# DM1097_LEFT_OV9282.net
KiCad netlist of a schematic drawn in Altium Designer
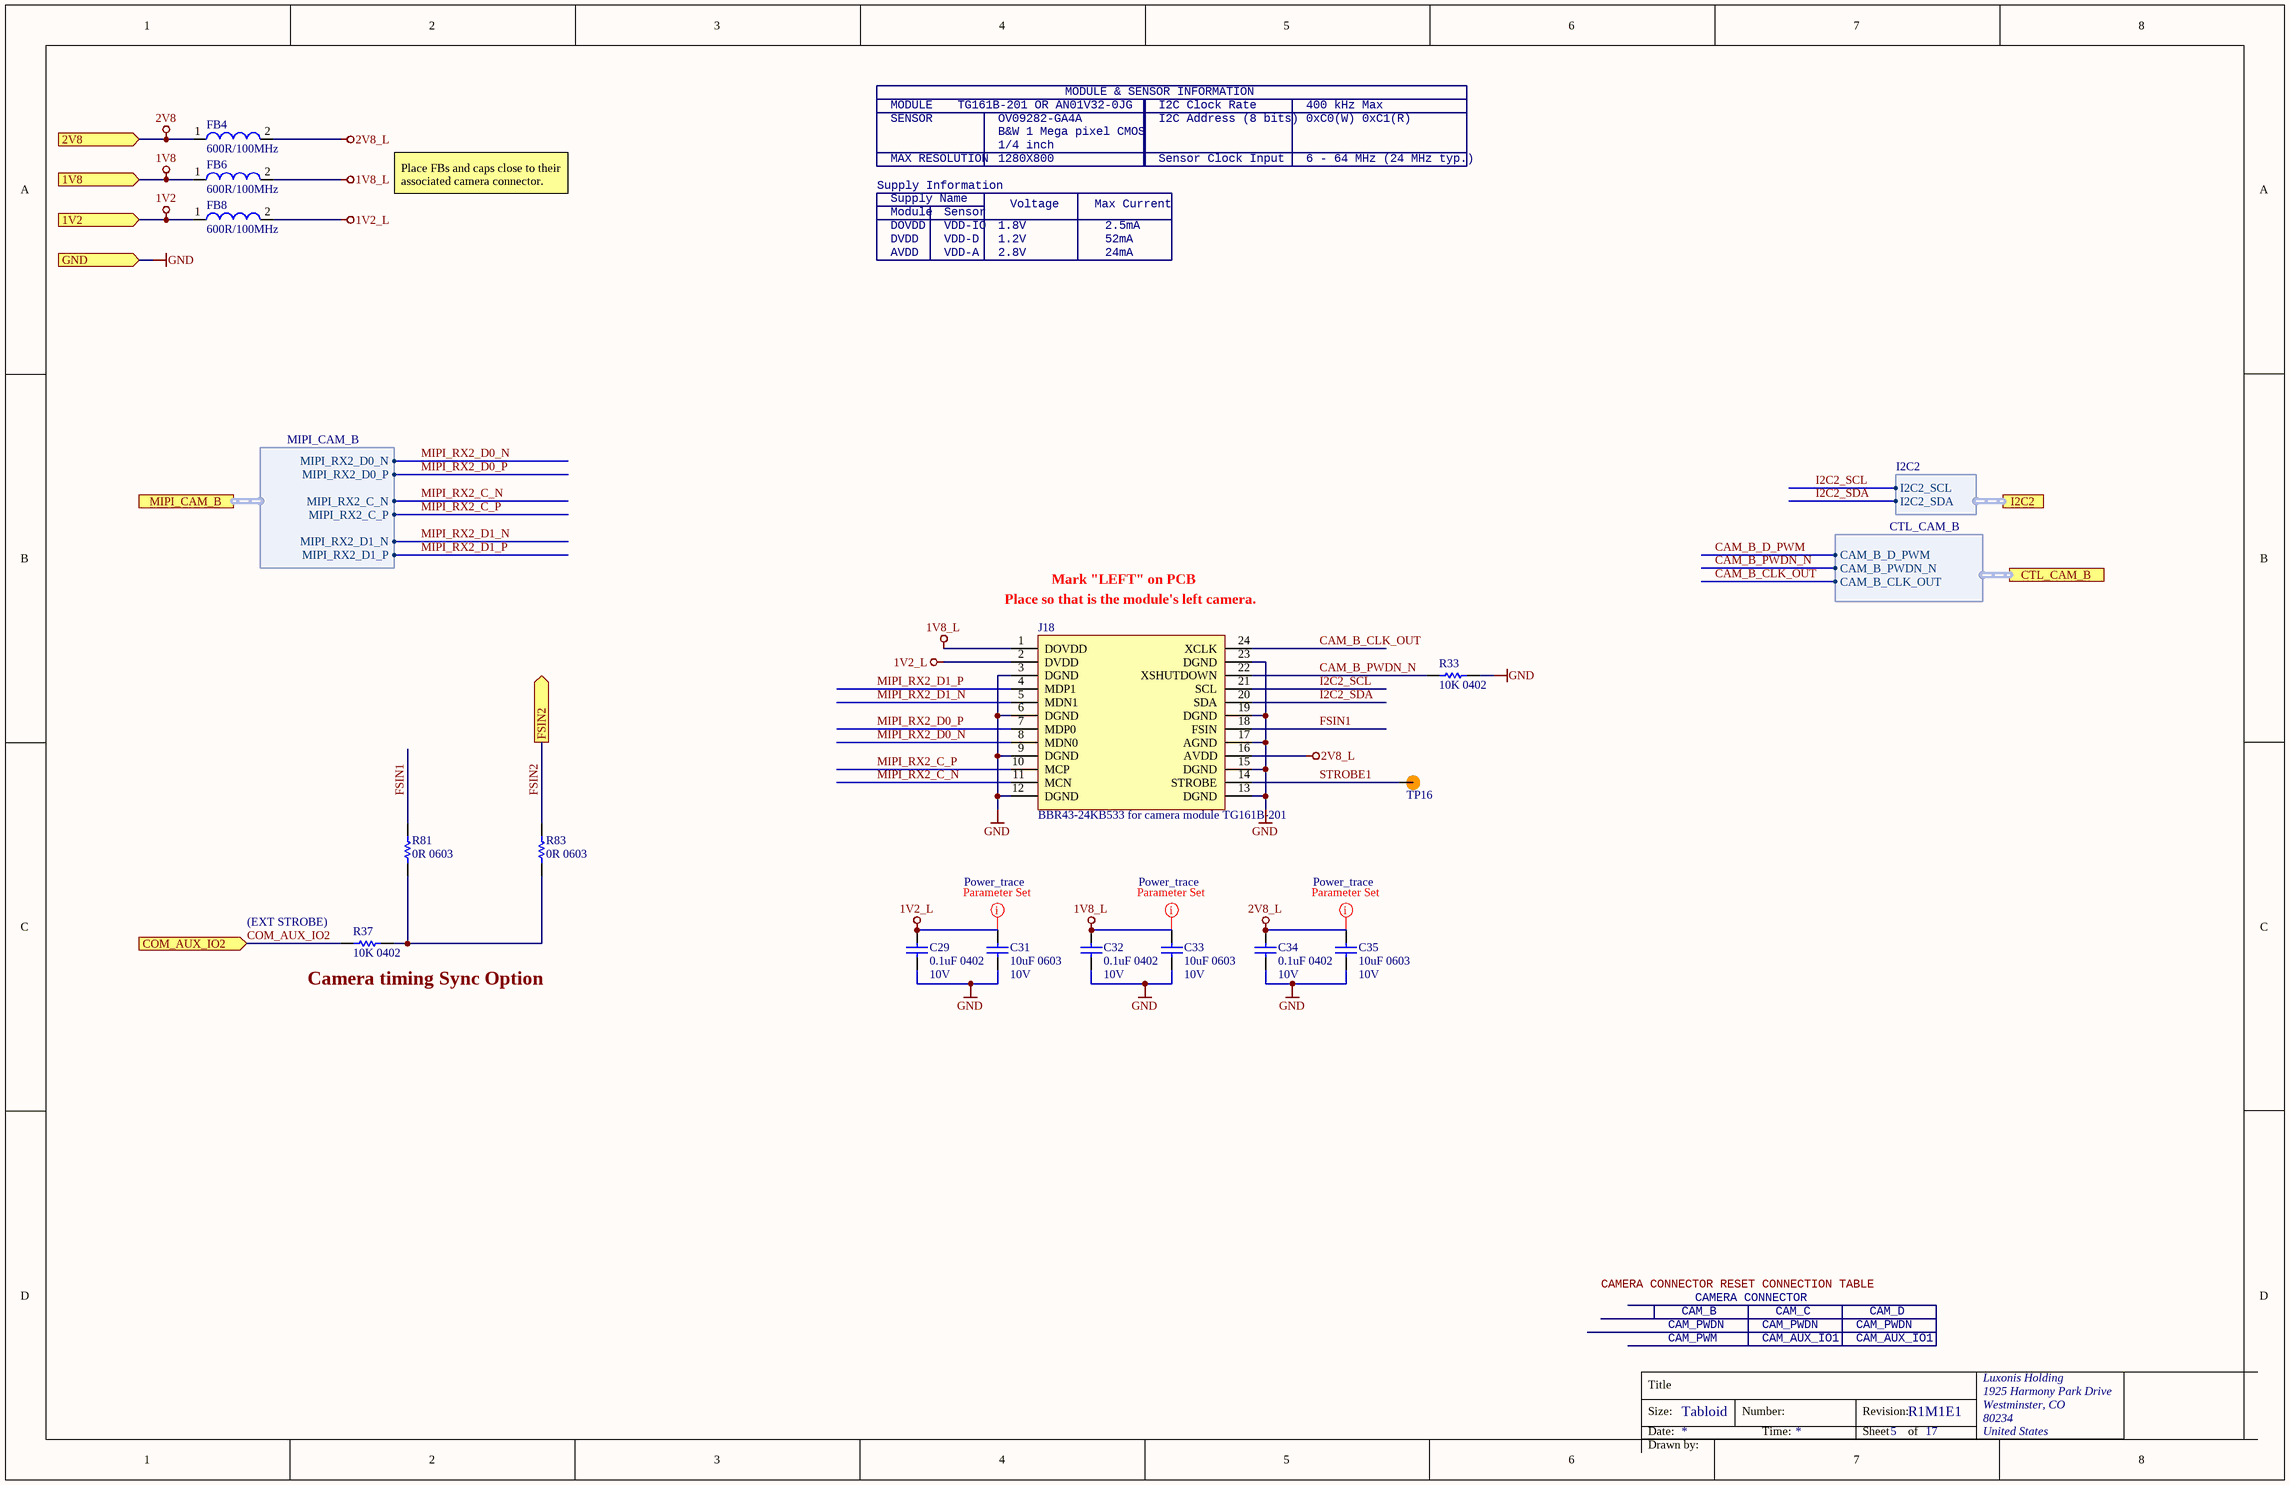
[diagram p0: DM1097_LEFT_OV9282.SchDoc]

(export (version "E")
  (design (tool "Eeschema 10.0.6"))
  (components
    (comp (ref "C29")
      (value "0.1uF 0402")
      (footprint "CAP_Altium_Vault_Generic:CAPC0402(1005)70_N")
      (description "CAP CER 0.1UF 10V X7R 0402 5%")
      (fields (field (name "TOLERANCE") "5%") (field (name "VOLTAGE RATING") "10V"))
      (libsource (lib "LuxonisMaster") (part "GRM155R71A104JA01D"))
    )
    (comp (ref "C31")
      (value "10uF 0603")
      (footprint "CAP_Altium_Vault_Generic:CAPC0603(1608)100_N")
      (description "CAP CER 10UF 10V X5R 0603 20%")
      (fields (field (name "TOLERANCE") "20%") (field (name "VOLTAGE RATING") "10V"))
      (libsource (lib "LuxonisMaster") (part "GRM188R61A106ME69D"))
    )
    (comp (ref "C32")
      (value "0.1uF 0402")
      (footprint "CAP_Altium_Vault_Generic:CAPC0402(1005)70_N")
      (description "CAP CER 0.1UF 10V X7R 0402 5%")
      (fields (field (name "TOLERANCE") "5%") (field (name "VOLTAGE RATING") "10V"))
      (libsource (lib "LuxonisMaster") (part "GRM155R71A104JA01D"))
    )
    (comp (ref "C33")
      (value "10uF 0603")
      (footprint "CAP_Altium_Vault_Generic:CAPC0603(1608)100_N")
      (description "CAP CER 10UF 10V X5R 0603 20%")
      (fields (field (name "TOLERANCE") "20%") (field (name "VOLTAGE RATING") "10V"))
      (libsource (lib "LuxonisMaster") (part "GRM188R61A106ME69D"))
    )
    (comp (ref "C34")
      (value "0.1uF 0402")
      (footprint "CAP_Altium_Vault_Generic:CAPC0402(1005)70_N")
      (description "CAP CER 0.1UF 10V X7R 0402 5%")
      (fields (field (name "TOLERANCE") "5%") (field (name "VOLTAGE RATING") "10V"))
      (libsource (lib "LuxonisMaster") (part "GRM155R71A104JA01D"))
    )
    (comp (ref "C35")
      (value "10uF 0603")
      (footprint "CAP_Altium_Vault_Generic:CAPC0603(1608)100_N")
      (description "CAP CER 10UF 10V X5R 0603 20%")
      (fields (field (name "TOLERANCE") "20%") (field (name "VOLTAGE RATING") "10V"))
      (libsource (lib "LuxonisMaster") (part "GRM188R61A106ME69D"))
    )
    (comp (ref "FB4")
      (value "600R/100MHz")
      (footprint "LuxonisMaster:2508056017Y2")
      (description "FERRITE BEAD, 0.1OHM, 2A, 0805, 600R/100MHz")
      (fields (field (name "TOLERANCE") "25%"))
      (libsource (lib "LuxonisMaster") (part "2508056017Y2"))
    )
    (comp (ref "FB6")
      (value "600R/100MHz")
      (footprint "LuxonisMaster:2508056017Y2")
      (description "FERRITE BEAD, 0.1OHM, 2A, 0805, 600R/100MHz")
      (fields (field (name "TOLERANCE") "25%"))
      (libsource (lib "LuxonisMaster") (part "2508056017Y2"))
    )
    (comp (ref "FB8")
      (value "600R/100MHz")
      (footprint "LuxonisMaster:2508056017Y2")
      (description "FERRITE BEAD, 0.1OHM, 2A, 0805, 600R/100MHz")
      (fields (field (name "TOLERANCE") "25%"))
      (libsource (lib "LuxonisMaster") (part "2508056017Y2"))
    )
    (comp (ref "J18")
      (value "BBR43-24KB533 for camera module TG161B-201")
      (footprint "LuxonisMaster:TG161B-201 / AN01V32 - Board Wrap (7mm setback) MinPads")
      (description "CONN 24 way, 2 row board to board connector SMD")
      (libsource (lib "LuxonisMaster") (part "TG161B-201_Connector"))
    )
    (comp (ref "R33")
      (value "10K 0402")
      (footprint "RES_Altium_Vault_Generic:RESC0402(1005)_N")
      (fields (field (name "TOLERANCE") "1%"))
      (libsource (lib "LuxonisMaster") (part "RC0402FR-1310KL"))
    )
    (comp (ref "R37")
      (value "10K 0402")
      (footprint "RES_Altium_Vault_Generic:RESC0402(1005)_L")
      (fields (field (name "TOLERANCE") "1%"))
      (libsource (lib "LuxonisMaster") (part "RC0402FR-1310KL"))
    )
    (comp (ref "R81")
      (value "0R 0603")
      (footprint "RES_Altium_Vault_Generic:RESC0603(1608)_N")
      (fields (field (name "TOLERANCE") "5%"))
      (libsource (lib "LuxonisMaster") (part "CRCW06030000Z0EA"))
    )
    (comp (ref "R83")
      (value "0R 0603")
      (footprint "RES_Altium_Vault_Generic:RESC0603(1608)_N")
      (fields (field (name "TOLERANCE") "5%"))
      (libsource (lib "LuxonisMaster") (part "CRCW06030000Z0EA"))
    )
    (comp (ref "TP16")
      (value "TP100_200_NS")
      (footprint "LuxonisMaster:TP100_200_NS")
      (libsource (lib "LuxonisMaster") (part "TEST_POINT"))
    )
  )
  (nets
    (net (code "4") (name "/CAM_B_CLK_OUT") (class "Default")
      (node (ref "J18") (pin "24") (pinfunction "XCLK_24") (pintype "passive"))
    )
    (net (code "6") (name "/CAM_B_PWDN_N") (class "Default")
      (node (ref "J18") (pin "22") (pinfunction "XSHUTDOWN_22") (pintype "passive"))
      (node (ref "R33") (pin "1") (pinfunction "1_1") (pintype "passive"))
    )
    (net (code "7") (name "/COM_AUX_IO2") (class "Default")
      (node (ref "R37") (pin "1") (pinfunction "1_1") (pintype "passive"))
    )
    (net (code "8") (name "/FSIN1") (class "Default")
      (node (ref "J18") (pin "18") (pinfunction "FSIN_18") (pintype "passive"))
      (node (ref "R81") (pin "2") (pinfunction "2_2") (pintype "passive"))
    )
    (net (code "9") (name "/FSIN2") (class "Default")
      (node (ref "R83") (pin "2") (pinfunction "2_2") (pintype "passive"))
    )
    (net (code "10") (name "/I2C2_SCL") (class "Default")
      (node (ref "J18") (pin "21") (pinfunction "SCL_21") (pintype "passive"))
    )
    (net (code "11") (name "/I2C2_SDA") (class "Default")
      (node (ref "J18") (pin "20") (pinfunction "SDA_20") (pintype "passive"))
    )
    (net (code "12") (name "/MIPI_RX2_C_N") (class "Default")
      (node (ref "J18") (pin "11") (pinfunction "MCN_11") (pintype "passive"))
    )
    (net (code "13") (name "/MIPI_RX2_C_P") (class "Default")
      (node (ref "J18") (pin "10") (pinfunction "MCP_10") (pintype "passive"))
    )
    (net (code "14") (name "/MIPI_RX2_D0_N") (class "Default")
      (node (ref "J18") (pin "8") (pinfunction "MDN0_8") (pintype "passive"))
    )
    (net (code "15") (name "/MIPI_RX2_D0_P") (class "Default")
      (node (ref "J18") (pin "7") (pinfunction "MDP0_7") (pintype "passive"))
    )
    (net (code "16") (name "/MIPI_RX2_D1_N") (class "Default")
      (node (ref "J18") (pin "5") (pinfunction "MDN1_5") (pintype "passive"))
    )
    (net (code "17") (name "/MIPI_RX2_D1_P") (class "Default")
      (node (ref "J18") (pin "4") (pinfunction "MDP1_4") (pintype "passive"))
    )
    (net (code "18") (name "/STROBE1") (class "Default")
      (node (ref "J18") (pin "14") (pinfunction "STROBE_14") (pintype "passive"))
      (node (ref "TP16") (pin "1") (pintype "passive"))
    )
    (net (code "22") (name "1V2") (class "Default")
      (node (ref "FB8") (pin "1") (pinfunction "1_1") (pintype "passive"))
    )
    (net (code "23") (name "1V2_L") (class "Default")
      (node (ref "C29") (pin "2") (pinfunction "2_2") (pintype "passive"))
      (node (ref "C31") (pin "2") (pinfunction "2_2") (pintype "passive"))
      (node (ref "FB8") (pin "2") (pinfunction "2_2") (pintype "passive"))
      (node (ref "J18") (pin "2") (pinfunction "DVDD_2") (pintype "passive"))
    )
    (net (code "24") (name "1V8") (class "Default")
      (node (ref "FB6") (pin "1") (pinfunction "1_1") (pintype "passive"))
    )
    (net (code "25") (name "1V8_L") (class "Default")
      (node (ref "C32") (pin "2") (pinfunction "2_2") (pintype "passive"))
      (node (ref "C33") (pin "2") (pinfunction "2_2") (pintype "passive"))
      (node (ref "FB6") (pin "2") (pinfunction "2_2") (pintype "passive"))
      (node (ref "J18") (pin "1") (pinfunction "DOVDD_1") (pintype "passive"))
    )
    (net (code "26") (name "2V8") (class "Default")
      (node (ref "FB4") (pin "1") (pinfunction "1_1") (pintype "passive"))
    )
    (net (code "27") (name "2V8_L") (class "Default")
      (node (ref "C34") (pin "2") (pinfunction "2_2") (pintype "passive"))
      (node (ref "C35") (pin "2") (pinfunction "2_2") (pintype "passive"))
      (node (ref "FB4") (pin "2") (pinfunction "2_2") (pintype "passive"))
      (node (ref "J18") (pin "16") (pinfunction "AVDD_16") (pintype "passive"))
    )
    (net (code "28") (name "GND") (class "Default")
      (node (ref "C29") (pin "1") (pinfunction "1_1") (pintype "passive"))
      (node (ref "C31") (pin "1") (pinfunction "1_1") (pintype "passive"))
      (node (ref "C32") (pin "1") (pinfunction "1_1") (pintype "passive"))
      (node (ref "C33") (pin "1") (pinfunction "1_1") (pintype "passive"))
      (node (ref "C34") (pin "1") (pinfunction "1_1") (pintype "passive"))
      (node (ref "C35") (pin "1") (pinfunction "1_1") (pintype "passive"))
      (node (ref "J18") (pin "12") (pinfunction "DGND_12") (pintype "passive"))
      (node (ref "J18") (pin "13") (pinfunction "DGND_13") (pintype "passive"))
      (node (ref "J18") (pin "15") (pinfunction "DGND_15") (pintype "passive"))
      (node (ref "J18") (pin "17") (pinfunction "AGND_17") (pintype "passive"))
      (node (ref "J18") (pin "19") (pinfunction "DGND_19") (pintype "passive"))
      (node (ref "J18") (pin "23") (pinfunction "DGND_23") (pintype "passive"))
      (node (ref "J18") (pin "3") (pinfunction "DGND_3") (pintype "passive"))
      (node (ref "J18") (pin "6") (pinfunction "DGND_6") (pintype "passive"))
      (node (ref "J18") (pin "9") (pinfunction "DGND_9") (pintype "passive"))
      (node (ref "R33") (pin "2") (pinfunction "2_2") (pintype "passive"))
    )
    (net (code "29") (name "Net-(R37-Pad2)") (class "Default")
      (node (ref "R37") (pin "2") (pinfunction "2_2") (pintype "passive"))
      (node (ref "R81") (pin "1") (pinfunction "1_1") (pintype "passive"))
      (node (ref "R83") (pin "1") (pinfunction "1_1") (pintype "passive"))
    )
  )
)
